# 2_port.net
KiCad netlist of a schematic drawn in EAGLE
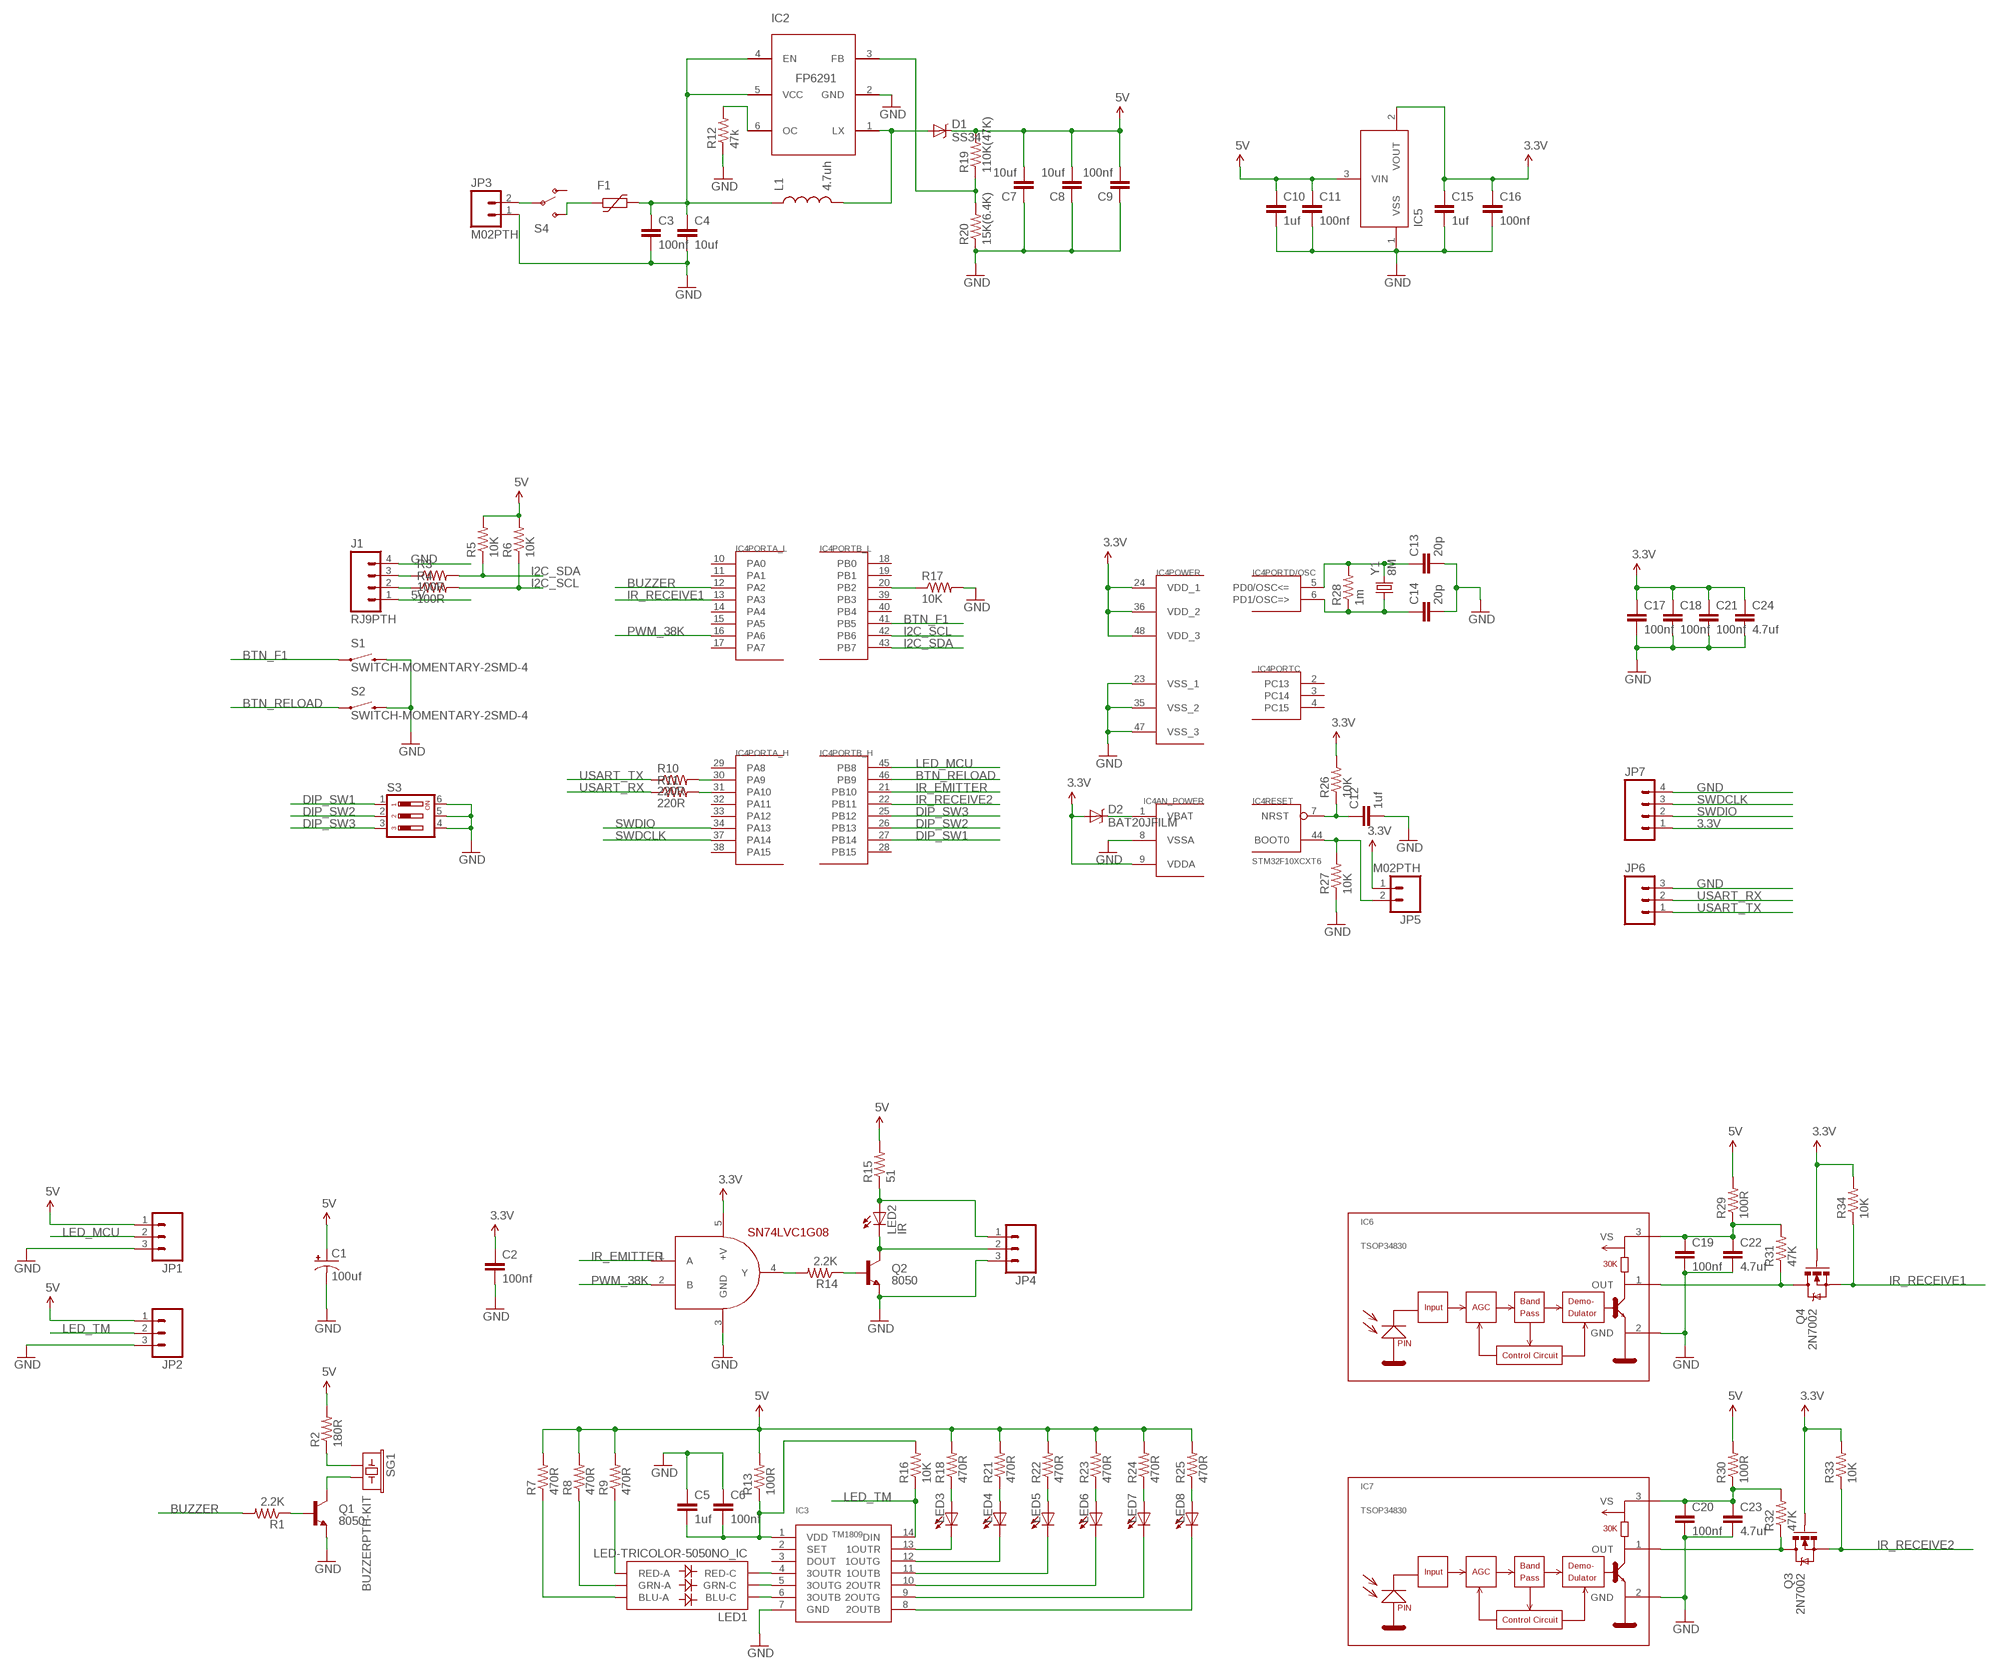
[diagram p0: schematic, sheet 1]

(export (version "E")
  (design (tool "Eeschema 10.0.6"))
  (components
    (comp (ref "C1")
      (value "100uf")
      (footprint "eagle-import:EIA6032")
      (libsource (lib "eagle-import") (part "CAP_POL6032"))
    )
    (comp (ref "C2")
      (value "100nf")
      (footprint "eagle-import:0603-CAP")
      (libsource (lib "eagle-import") (part "CAP0603-CAP"))
    )
    (comp (ref "C3")
      (value "100nf")
      (footprint "eagle-import:0603-CAP")
      (libsource (lib "eagle-import") (part "CAP0603-CAP"))
    )
    (comp (ref "C4")
      (value "10uf")
      (footprint "eagle-import:0603-CAP")
      (libsource (lib "eagle-import") (part "CAP0603-CAP"))
    )
    (comp (ref "C5")
      (value "1uf")
      (footprint "eagle-import:0603-CAP")
      (libsource (lib "eagle-import") (part "CAP0603-CAP"))
    )
    (comp (ref "C6")
      (value "100nf")
      (footprint "eagle-import:0603-CAP")
      (libsource (lib "eagle-import") (part "CAP0603-CAP"))
    )
    (comp (ref "C7")
      (value "10uf")
      (footprint "eagle-import:0603-CAP")
      (libsource (lib "eagle-import") (part "CAP0603-CAP"))
    )
    (comp (ref "C8")
      (value "10uf")
      (footprint "eagle-import:0603-CAP")
      (libsource (lib "eagle-import") (part "CAP0603-CAP"))
    )
    (comp (ref "C9")
      (value "100nf")
      (footprint "eagle-import:0603-CAP")
      (libsource (lib "eagle-import") (part "CAP0603-CAP"))
    )
    (comp (ref "C10")
      (value "1uf")
      (footprint "eagle-import:0603-CAP")
      (libsource (lib "eagle-import") (part "CAP0603-CAP"))
    )
    (comp (ref "C11")
      (value "100nf")
      (footprint "eagle-import:0603-CAP")
      (libsource (lib "eagle-import") (part "CAP0603-CAP"))
    )
    (comp (ref "C12")
      (value "1uf")
      (footprint "eagle-import:0603-CAP")
      (libsource (lib "eagle-import") (part "CAP0603-CAP"))
    )
    (comp (ref "C13")
      (value "20p")
      (footprint "eagle-import:0603-CAP")
      (libsource (lib "eagle-import") (part "CAP0603-CAP"))
    )
    (comp (ref "C14")
      (value "20p")
      (footprint "eagle-import:0603-CAP")
      (libsource (lib "eagle-import") (part "CAP0603-CAP"))
    )
    (comp (ref "C15")
      (value "1uf")
      (footprint "eagle-import:0603-CAP")
      (libsource (lib "eagle-import") (part "CAP0603-CAP"))
    )
    (comp (ref "C16")
      (value "100nf")
      (footprint "eagle-import:0603-CAP")
      (libsource (lib "eagle-import") (part "CAP0603-CAP"))
    )
    (comp (ref "C17")
      (value "100nf")
      (footprint "eagle-import:0603-CAP")
      (libsource (lib "eagle-import") (part "CAP0603-CAP"))
    )
    (comp (ref "C18")
      (value "100nf")
      (footprint "eagle-import:0603-CAP")
      (libsource (lib "eagle-import") (part "CAP0603-CAP"))
    )
    (comp (ref "C19")
      (value "100nf")
      (footprint "eagle-import:0603-CAP")
      (libsource (lib "eagle-import") (part "CAP0603-CAP"))
    )
    (comp (ref "C20")
      (value "100nf")
      (footprint "eagle-import:0603-CAP")
      (libsource (lib "eagle-import") (part "CAP0603-CAP"))
    )
    (comp (ref "C21")
      (value "100nf")
      (footprint "eagle-import:0603-CAP")
      (libsource (lib "eagle-import") (part "CAP0603-CAP"))
    )
    (comp (ref "C22")
      (value "4.7uf")
      (footprint "eagle-import:0603-CAP")
      (libsource (lib "eagle-import") (part "CAP0603-CAP"))
    )
    (comp (ref "C23")
      (value "4.7uf")
      (footprint "eagle-import:0603-CAP")
      (libsource (lib "eagle-import") (part "CAP0603-CAP"))
    )
    (comp (ref "C24")
      (value "4.7uf")
      (footprint "eagle-import:0603-CAP")
      (libsource (lib "eagle-import") (part "CAP0603-CAP"))
    )
    (comp (ref "D1")
      (value "SS34")
      (footprint "eagle-import:SMA-DIODE")
      (libsource (lib "eagle-import") (part "DIODE-SCHOTTKY_"))
    )
    (comp (ref "D2")
      (value "BAT20JFILM")
      (footprint "eagle-import:SOD-323")
      (libsource (lib "eagle-import") (part "BAT20JFILM"))
    )
    (comp (ref "F1")
      (value "PTC-FUSE")
      (footprint "eagle-import:R0805")
      (libsource (lib "eagle-import") (part "PTC-FUSE"))
    )
    (comp (ref "IC1")
      (value "SN74LVC1G08")
      (footprint "eagle-import:SOT23-5")
      (libsource (lib "eagle-import") (part "SN74LVC1G08"))
    )
    (comp (ref "IC2")
      (value "FP6291")
      (footprint "eagle-import:SOT23-6")
      (libsource (lib "eagle-import") (part "FP6291"))
    )
    (comp (ref "IC3")
      (value "TM1809")
      (footprint "eagle-import:SOP-14")
      (libsource (lib "eagle-import") (part "TM1809"))
    )
    (comp (ref "IC4")
      (value "STM32F10XCXT6")
      (footprint "eagle-import:TQFP48")
      (libsource (lib "eagle-import") (part "STM32F10XCXT6"))
    )
    (comp (ref "IC5")
      (value "XC6206")
      (footprint "eagle-import:SOT23-3")
      (libsource (lib "eagle-import") (part "XC6206"))
    )
    (comp (ref "IC6")
      (value "TSOP34830")
      (footprint "eagle-import:TSOP348")
      (libsource (lib "eagle-import") (part "TSOP34830"))
    )
    (comp (ref "IC7")
      (value "TSOP34830")
      (footprint "eagle-import:TSOP348")
      (libsource (lib "eagle-import") (part "TSOP34830"))
    )
    (comp (ref "J1")
      (value "RJ9PTH")
      (footprint "eagle-import:RJ9")
      (libsource (lib "eagle-import") (part "RJ9PTH"))
    )
    (comp (ref "JP1")
      (value "M03PTH")
      (footprint "eagle-import:1X03")
      (libsource (lib "eagle-import") (part "M03PTH"))
    )
    (comp (ref "JP2")
      (value "M03PTH")
      (footprint "eagle-import:1X03")
      (libsource (lib "eagle-import") (part "M03PTH"))
    )
    (comp (ref "JP3")
      (value "M02PTH")
      (footprint "eagle-import:1X02")
      (libsource (lib "eagle-import") (part "M02PTH"))
    )
    (comp (ref "JP4")
      (value "M03PTH")
      (footprint "eagle-import:1X03")
      (libsource (lib "eagle-import") (part "M03PTH"))
    )
    (comp (ref "JP5")
      (value "M02PTH")
      (footprint "eagle-import:1X02")
      (libsource (lib "eagle-import") (part "M02PTH"))
    )
    (comp (ref "JP6")
      (value "M03PTH")
      (footprint "eagle-import:1X03")
      (libsource (lib "eagle-import") (part "M03PTH"))
    )
    (comp (ref "JP7")
      (value "M04PTH")
      (footprint "eagle-import:1X04")
      (libsource (lib "eagle-import") (part "M04PTH"))
    )
    (comp (ref "L1")
      (value "4.7uh")
      (footprint "eagle-import:CR75_V2")
      (libsource (lib "eagle-import") (part "INDUCTORCR75_V2"))
    )
    (comp (ref "LED1")
      (value "LED-TRICOLOR-5050NO_IC")
      (footprint "eagle-import:LED-TRICOLOR-5050")
      (libsource (lib "eagle-import") (part "LED-TRICOLOR-5050NO_IC"))
    )
    (comp (ref "LED2")
      (value "IR")
      (footprint "eagle-import:LED5MM")
      (libsource (lib "eagle-import") (part "LED5MM"))
    )
    (comp (ref "LED3")
      (value "LED0805")
      (footprint "eagle-import:CHIPLED_0805")
      (libsource (lib "eagle-import") (part "LED0805"))
    )
    (comp (ref "LED4")
      (value "LED0805")
      (footprint "eagle-import:CHIPLED_0805")
      (libsource (lib "eagle-import") (part "LED0805"))
    )
    (comp (ref "LED5")
      (value "LED0805")
      (footprint "eagle-import:CHIPLED_0805")
      (libsource (lib "eagle-import") (part "LED0805"))
    )
    (comp (ref "LED6")
      (value "LED0805")
      (footprint "eagle-import:CHIPLED_0805")
      (libsource (lib "eagle-import") (part "LED0805"))
    )
    (comp (ref "LED7")
      (value "LED0805")
      (footprint "eagle-import:CHIPLED_0805")
      (libsource (lib "eagle-import") (part "LED0805"))
    )
    (comp (ref "LED8")
      (value "LED0805")
      (footprint "eagle-import:CHIPLED_0805")
      (libsource (lib "eagle-import") (part "LED0805"))
    )
    (comp (ref "Q1")
      (value "8050")
      (footprint "eagle-import:SOT23")
      (libsource (lib "eagle-import") (part "TRANSISTOR_NPNSOT23"))
    )
    (comp (ref "Q2")
      (value "8050")
      (footprint "eagle-import:SOT23")
      (libsource (lib "eagle-import") (part "TRANSISTOR_NPNSOT23"))
    )
    (comp (ref "Q3")
      (value "2N7002")
      (footprint "eagle-import:SOT23")
      (libsource (lib "eagle-import") (part "MOSFET-NCHANNELBSS138"))
    )
    (comp (ref "Q4")
      (value "2N7002")
      (footprint "eagle-import:SOT23")
      (libsource (lib "eagle-import") (part "MOSFET-NCHANNELBSS138"))
    )
    (comp (ref "R1")
      (value "2.2K")
      (footprint "eagle-import:0603-RES")
      (libsource (lib "eagle-import") (part "RESISTOR0603-RES"))
    )
    (comp (ref "R2")
      (value "180R")
      (footprint "eagle-import:0603-RES")
      (libsource (lib "eagle-import") (part "RESISTOR0603-RES"))
    )
    (comp (ref "R3")
      (value "100R")
      (footprint "eagle-import:0603-RES")
      (libsource (lib "eagle-import") (part "RESISTOR0603-RES"))
    )
    (comp (ref "R4")
      (value "100R")
      (footprint "eagle-import:0603-RES")
      (libsource (lib "eagle-import") (part "RESISTOR0603-RES"))
    )
    (comp (ref "R5")
      (value "10K")
      (footprint "eagle-import:0603-RES")
      (libsource (lib "eagle-import") (part "RESISTOR0603-RES"))
    )
    (comp (ref "R6")
      (value "10K")
      (footprint "eagle-import:0603-RES")
      (libsource (lib "eagle-import") (part "RESISTOR0603-RES"))
    )
    (comp (ref "R7")
      (value "470R")
      (footprint "eagle-import:0603-RES")
      (libsource (lib "eagle-import") (part "RESISTOR0603-RES"))
    )
    (comp (ref "R8")
      (value "470R")
      (footprint "eagle-import:0603-RES")
      (libsource (lib "eagle-import") (part "RESISTOR0603-RES"))
    )
    (comp (ref "R9")
      (value "470R")
      (footprint "eagle-import:0603-RES")
      (libsource (lib "eagle-import") (part "RESISTOR0603-RES"))
    )
    (comp (ref "R10")
      (value "220R")
      (footprint "eagle-import:0603-RES")
      (libsource (lib "eagle-import") (part "RESISTOR0603-RES"))
    )
    (comp (ref "R11")
      (value "220R")
      (footprint "eagle-import:0603-RES")
      (libsource (lib "eagle-import") (part "RESISTOR0603-RES"))
    )
    (comp (ref "R12")
      (value "47k")
      (footprint "eagle-import:0603-RES")
      (libsource (lib "eagle-import") (part "RESISTOR0603-RES"))
    )
    (comp (ref "R13")
      (value "100R")
      (footprint "eagle-import:0603-RES")
      (libsource (lib "eagle-import") (part "RESISTOR0603-RES"))
    )
    (comp (ref "R14")
      (value "2.2K")
      (footprint "eagle-import:0603-RES")
      (libsource (lib "eagle-import") (part "RESISTOR0603-RES"))
    )
    (comp (ref "R15")
      (value "51")
      (footprint "eagle-import:1206")
      (libsource (lib "eagle-import") (part "SparkFun-Resistors_RESISTOR1206"))
    )
    (comp (ref "R16")
      (value "10K")
      (footprint "eagle-import:0603-RES")
      (libsource (lib "eagle-import") (part "RESISTOR0603-RES"))
    )
    (comp (ref "R17")
      (value "10K")
      (footprint "eagle-import:0603-RES")
      (libsource (lib "eagle-import") (part "RESISTOR0603-RES"))
    )
    (comp (ref "R18")
      (value "470R")
      (footprint "eagle-import:0603-RES")
      (libsource (lib "eagle-import") (part "RESISTOR0603-RES"))
    )
    (comp (ref "R19")
      (value "110K(47K)")
      (footprint "eagle-import:0603-RES")
      (libsource (lib "eagle-import") (part "RESISTOR0603-RES"))
    )
    (comp (ref "R20")
      (value "15K(6.4K)")
      (footprint "eagle-import:0603-RES")
      (libsource (lib "eagle-import") (part "RESISTOR0603-RES"))
    )
    (comp (ref "R21")
      (value "470R")
      (footprint "eagle-import:0603-RES")
      (libsource (lib "eagle-import") (part "RESISTOR0603-RES"))
    )
    (comp (ref "R22")
      (value "470R")
      (footprint "eagle-import:0603-RES")
      (libsource (lib "eagle-import") (part "RESISTOR0603-RES"))
    )
    (comp (ref "R23")
      (value "470R")
      (footprint "eagle-import:0603-RES")
      (libsource (lib "eagle-import") (part "RESISTOR0603-RES"))
    )
    (comp (ref "R24")
      (value "470R")
      (footprint "eagle-import:0603-RES")
      (libsource (lib "eagle-import") (part "RESISTOR0603-RES"))
    )
    (comp (ref "R25")
      (value "470R")
      (footprint "eagle-import:0603-RES")
      (libsource (lib "eagle-import") (part "RESISTOR0603-RES"))
    )
    (comp (ref "R26")
      (value "10K")
      (footprint "eagle-import:0603-RES")
      (libsource (lib "eagle-import") (part "RESISTOR0603-RES"))
    )
    (comp (ref "R27")
      (value "10K")
      (footprint "eagle-import:0603-RES")
      (libsource (lib "eagle-import") (part "RESISTOR0603-RES"))
    )
    (comp (ref "R28")
      (value "1m")
      (footprint "eagle-import:0603-RES")
      (libsource (lib "eagle-import") (part "RESISTOR0603-RES"))
    )
    (comp (ref "R29")
      (value "100R")
      (footprint "eagle-import:0603-RES")
      (libsource (lib "eagle-import") (part "RESISTOR0603-RES"))
    )
    (comp (ref "R30")
      (value "100R")
      (footprint "eagle-import:0603-RES")
      (libsource (lib "eagle-import") (part "RESISTOR0603-RES"))
    )
    (comp (ref "R31")
      (value "47K")
      (footprint "eagle-import:0603-RES")
      (libsource (lib "eagle-import") (part "RESISTOR0603-RES"))
    )
    (comp (ref "R32")
      (value "47K")
      (footprint "eagle-import:0603-RES")
      (libsource (lib "eagle-import") (part "RESISTOR0603-RES"))
    )
    (comp (ref "R33")
      (value "10K")
      (footprint "eagle-import:0603-RES")
      (libsource (lib "eagle-import") (part "RESISTOR0603-RES"))
    )
    (comp (ref "R34")
      (value "10K")
      (footprint "eagle-import:0603-RES")
      (libsource (lib "eagle-import") (part "RESISTOR0603-RES"))
    )
    (comp (ref "S1")
      (value "SWITCH-MOMENTARY-2SMD-4")
      (footprint "eagle-import:TACTILE_SWITCH_TALL")
      (libsource (lib "eagle-import") (part "SWITCH-MOMENTARY-2SMD-4"))
    )
    (comp (ref "S2")
      (value "SWITCH-MOMENTARY-2SMD-4")
      (footprint "eagle-import:TACTILE_SWITCH_TALL")
      (libsource (lib "eagle-import") (part "SWITCH-MOMENTARY-2SMD-4"))
    )
    (comp (ref "S3")
      (value "DIP03YL")
      (footprint "eagle-import:DIP03YL")
      (libsource (lib "eagle-import") (part "DIP03YL"))
    )
    (comp (ref "S4")
      (value "SWITCH-SPST3AM6")
      (footprint "eagle-import:SWITCH-SPDT-AM#6")
      (libsource (lib "eagle-import") (part "SWITCH-SPST3AM6"))
    )
    (comp (ref "SG1")
      (value "BUZZERPTH-KIT")
      (footprint "eagle-import:BUZZER-12MM-KIT")
      (libsource (lib "eagle-import") (part "BUZZERPTH-KIT"))
    )
    (comp (ref "Y1")
      (value "8M")
      (footprint "eagle-import:CRYSTAL-TXC-7A")
      (libsource (lib "eagle-import") (part "CRYSTALTXC-7A"))
    )
  )
  (nets
    (net (code "1") (name "/BTN_F1") (class "Default")
      (node (ref "IC4") (pin "41") (pinfunction "PB5_41") (pintype "bidirectional"))
      (node (ref "S1") (pin "A2") (pinfunction "1_A2") (pintype "passive"))
    )
    (net (code "2") (name "/BTN_RELOAD") (class "Default")
      (node (ref "IC4") (pin "46") (pinfunction "PB9_46") (pintype "bidirectional"))
      (node (ref "S2") (pin "A2") (pinfunction "1_A2") (pintype "passive"))
    )
    (net (code "3") (name "/BUZZER") (class "Default")
      (node (ref "IC4") (pin "12") (pinfunction "PA2_12") (pintype "bidirectional"))
      (node (ref "R1") (pin "2") (pinfunction "2_2") (pintype "passive"))
    )
    (net (code "4") (name "/DIP_SW1") (class "Default")
      (node (ref "IC4") (pin "27") (pinfunction "PB14_27") (pintype "bidirectional"))
      (node (ref "S3") (pin "1") (pinfunction "1_1") (pintype "passive"))
    )
    (net (code "5") (name "/DIP_SW2") (class "Default")
      (node (ref "IC4") (pin "26") (pinfunction "PB13_26") (pintype "bidirectional"))
      (node (ref "S3") (pin "2") (pinfunction "2_2") (pintype "passive"))
    )
    (net (code "6") (name "/DIP_SW3") (class "Default")
      (node (ref "IC4") (pin "25") (pinfunction "PB12_25") (pintype "bidirectional"))
      (node (ref "S3") (pin "3") (pinfunction "3_3") (pintype "passive"))
    )
    (net (code "7") (name "/I2C_SCL") (class "Default")
      (node (ref "IC4") (pin "42") (pinfunction "PB6_42") (pintype "bidirectional"))
      (node (ref "R4") (pin "2") (pinfunction "2_2") (pintype "passive"))
      (node (ref "R6") (pin "1") (pinfunction "1_1") (pintype "passive"))
    )
    (net (code "8") (name "/I2C_SDA") (class "Default")
      (node (ref "IC4") (pin "43") (pinfunction "PB7_43") (pintype "bidirectional"))
      (node (ref "R3") (pin "2") (pinfunction "2_2") (pintype "passive"))
      (node (ref "R5") (pin "1") (pinfunction "1_1") (pintype "passive"))
    )
    (net (code "9") (name "/IR_EMITTER") (class "Default")
      (node (ref "IC1") (pin "1") (pinfunction "A_1") (pintype "bidirectional"))
      (node (ref "IC4") (pin "21") (pinfunction "PB10_21") (pintype "bidirectional"))
    )
    (net (code "10") (name "/IR_RECEIVE1") (class "Default")
      (node (ref "IC4") (pin "13") (pinfunction "PA3_13") (pintype "bidirectional"))
      (node (ref "Q4") (pin "2") (pinfunction "S_2") (pintype "passive"))
      (node (ref "R34") (pin "1") (pinfunction "1_1") (pintype "passive"))
    )
    (net (code "11") (name "/IR_RECEIVE2") (class "Default")
      (node (ref "IC4") (pin "22") (pinfunction "PB11_22") (pintype "bidirectional"))
      (node (ref "Q3") (pin "2") (pinfunction "S_2") (pintype "passive"))
      (node (ref "R33") (pin "1") (pinfunction "1_1") (pintype "passive"))
    )
    (net (code "12") (name "/LED_MCU") (class "Default")
      (node (ref "IC4") (pin "45") (pinfunction "PB8_45") (pintype "bidirectional"))
      (node (ref "JP1") (pin "2") (pinfunction "2_2") (pintype "passive"))
    )
    (net (code "13") (name "/LED_TM") (class "Default")
      (node (ref "IC3") (pin "14") (pinfunction "DIN_14") (pintype "input"))
      (node (ref "JP2") (pin "2") (pinfunction "2_2") (pintype "passive"))
      (node (ref "R16") (pin "1") (pinfunction "1_1") (pintype "passive"))
    )
    (net (code "14") (name "/PWM_38K") (class "Default")
      (node (ref "IC1") (pin "2") (pinfunction "B_2") (pintype "bidirectional"))
      (node (ref "IC4") (pin "16") (pinfunction "PA6_16") (pintype "bidirectional"))
    )
    (net (code "15") (name "/SWDCLK") (class "Default")
      (node (ref "IC4") (pin "37") (pinfunction "PA14_37") (pintype "bidirectional"))
      (node (ref "JP7") (pin "3") (pinfunction "3_3") (pintype "passive"))
    )
    (net (code "16") (name "/SWDIO") (class "Default")
      (node (ref "IC4") (pin "34") (pinfunction "PA13_34") (pintype "bidirectional"))
      (node (ref "JP7") (pin "2") (pinfunction "2_2") (pintype "passive"))
    )
    (net (code "17") (name "/USART_RX") (class "Default")
      (node (ref "JP6") (pin "2") (pinfunction "2_2") (pintype "passive"))
      (node (ref "R11") (pin "1") (pinfunction "1_1") (pintype "passive"))
    )
    (net (code "18") (name "/USART_TX") (class "Default")
      (node (ref "JP6") (pin "1") (pinfunction "1_1") (pintype "passive"))
      (node (ref "R10") (pin "1") (pinfunction "1_1") (pintype "passive"))
    )
    (net (code "19") (name "3.3V") (class "Default")
      (node (ref "C15") (pin "1") (pinfunction "1_1") (pintype "passive"))
      (node (ref "C16") (pin "1") (pinfunction "1_1") (pintype "passive"))
      (node (ref "C17") (pin "1") (pinfunction "1_1") (pintype "passive"))
      (node (ref "C18") (pin "1") (pinfunction "1_1") (pintype "passive"))
      (node (ref "C2") (pin "1") (pinfunction "1_1") (pintype "passive"))
      (node (ref "C21") (pin "1") (pinfunction "1_1") (pintype "passive"))
      (node (ref "C24") (pin "1") (pinfunction "1_1") (pintype "passive"))
      (node (ref "D2") (pin "2") (pinfunction "A_2") (pintype "passive"))
      (node (ref "IC1") (pin "5") (pinfunction "+V_5") (pintype "bidirectional"))
      (node (ref "IC4") (pin "24") (pinfunction "VDD_1_24") (pintype "power_in"))
      (node (ref "IC4") (pin "36") (pinfunction "VDD_2_36") (pintype "power_in"))
      (node (ref "IC4") (pin "48") (pinfunction "VDD_3_48") (pintype "power_in"))
      (node (ref "IC4") (pin "9") (pinfunction "VDDA_9") (pintype "power_in"))
      (node (ref "IC5") (pin "2") (pinfunction "VOUT_2") (pintype "power_in"))
      (node (ref "JP5") (pin "1") (pinfunction "1_1") (pintype "passive"))
      (node (ref "JP7") (pin "1") (pinfunction "1_1") (pintype "passive"))
      (node (ref "Q3") (pin "1") (pinfunction "G_1") (pintype "passive"))
      (node (ref "Q4") (pin "1") (pinfunction "G_1") (pintype "passive"))
      (node (ref "R26") (pin "2") (pinfunction "2_2") (pintype "passive"))
      (node (ref "R33") (pin "2") (pinfunction "2_2") (pintype "passive"))
      (node (ref "R34") (pin "2") (pinfunction "2_2") (pintype "passive"))
    )
    (net (code "20") (name "5V") (class "Default")
      (node (ref "C1") (pin "P$1") (pinfunction "+_P$1") (pintype "passive"))
      (node (ref "C10") (pin "1") (pinfunction "1_1") (pintype "passive"))
      (node (ref "C11") (pin "1") (pinfunction "1_1") (pintype "passive"))
      (node (ref "C7") (pin "2") (pinfunction "2_2") (pintype "passive"))
      (node (ref "C8") (pin "2") (pinfunction "2_2") (pintype "passive"))
      (node (ref "C9") (pin "2") (pinfunction "2_2") (pintype "passive"))
      (node (ref "D1") (pin "C") (pinfunction "C_C") (pintype "passive"))
      (node (ref "IC5") (pin "3") (pinfunction "VIN_3") (pintype "power_in"))
      (node (ref "J1") (pin "1") (pinfunction "1_1") (pintype "passive"))
      (node (ref "JP1") (pin "1") (pinfunction "1_1") (pintype "passive"))
      (node (ref "JP2") (pin "1") (pinfunction "1_1") (pintype "passive"))
      (node (ref "R13") (pin "2") (pinfunction "2_2") (pintype "passive"))
      (node (ref "R15") (pin "2") (pinfunction "2_2") (pintype "passive"))
      (node (ref "R18") (pin "2") (pinfunction "2_2") (pintype "passive"))
      (node (ref "R19") (pin "2") (pinfunction "2_2") (pintype "passive"))
      (node (ref "R2") (pin "2") (pinfunction "2_2") (pintype "passive"))
      (node (ref "R21") (pin "2") (pinfunction "2_2") (pintype "passive"))
      (node (ref "R22") (pin "2") (pinfunction "2_2") (pintype "passive"))
      (node (ref "R23") (pin "2") (pinfunction "2_2") (pintype "passive"))
      (node (ref "R24") (pin "2") (pinfunction "2_2") (pintype "passive"))
      (node (ref "R25") (pin "2") (pinfunction "2_2") (pintype "passive"))
      (node (ref "R29") (pin "2") (pinfunction "2_2") (pintype "passive"))
      (node (ref "R30") (pin "2") (pinfunction "2_2") (pintype "passive"))
      (node (ref "R5") (pin "2") (pinfunction "2_2") (pintype "passive"))
      (node (ref "R6") (pin "2") (pinfunction "2_2") (pintype "passive"))
      (node (ref "R7") (pin "2") (pinfunction "2_2") (pintype "passive"))
      (node (ref "R8") (pin "2") (pinfunction "2_2") (pintype "passive"))
      (node (ref "R9") (pin "2") (pinfunction "2_2") (pintype "passive"))
    )
    (net (code "21") (name "GND") (class "Default")
      (node (ref "C1") (pin "P$2") (pinfunction "-_P$2") (pintype "passive"))
      (node (ref "C10") (pin "2") (pinfunction "2_2") (pintype "passive"))
      (node (ref "C11") (pin "2") (pinfunction "2_2") (pintype "passive"))
      (node (ref "C12") (pin "2") (pinfunction "2_2") (pintype "passive"))
      (node (ref "C13") (pin "2") (pinfunction "2_2") (pintype "passive"))
      (node (ref "C14") (pin "2") (pinfunction "2_2") (pintype "passive"))
      (node (ref "C15") (pin "2") (pinfunction "2_2") (pintype "passive"))
      (node (ref "C16") (pin "2") (pinfunction "2_2") (pintype "passive"))
      (node (ref "C17") (pin "2") (pinfunction "2_2") (pintype "passive"))
      (node (ref "C18") (pin "2") (pinfunction "2_2") (pintype "passive"))
      (node (ref "C19") (pin "2") (pinfunction "2_2") (pintype "passive"))
      (node (ref "C2") (pin "2") (pinfunction "2_2") (pintype "passive"))
      (node (ref "C20") (pin "2") (pinfunction "2_2") (pintype "passive"))
      (node (ref "C21") (pin "2") (pinfunction "2_2") (pintype "passive"))
      (node (ref "C22") (pin "2") (pinfunction "2_2") (pintype "passive"))
      (node (ref "C23") (pin "2") (pinfunction "2_2") (pintype "passive"))
      (node (ref "C24") (pin "2") (pinfunction "2_2") (pintype "passive"))
      (node (ref "C3") (pin "2") (pinfunction "2_2") (pintype "passive"))
      (node (ref "C4") (pin "2") (pinfunction "2_2") (pintype "passive"))
      (node (ref "C5") (pin "1") (pinfunction "1_1") (pintype "passive"))
      (node (ref "C6") (pin "1") (pinfunction "1_1") (pintype "passive"))
      (node (ref "C7") (pin "1") (pinfunction "1_1") (pintype "passive"))
      (node (ref "C8") (pin "1") (pinfunction "1_1") (pintype "passive"))
      (node (ref "C9") (pin "1") (pinfunction "1_1") (pintype "passive"))
      (node (ref "IC1") (pin "3") (pinfunction "GND_3") (pintype "bidirectional"))
      (node (ref "IC2") (pin "2") (pinfunction "GND_2") (pintype "power_in"))
      (node (ref "IC3") (pin "7") (pinfunction "GND_7") (pintype "power_in"))
      (node (ref "IC4") (pin "23") (pinfunction "VSS_1_23") (pintype "power_in"))
      (node (ref "IC4") (pin "35") (pinfunction "VSS_2_35") (pintype "power_in"))
      (node (ref "IC4") (pin "47") (pinfunction "VSS_3_47") (pintype "power_in"))
      (node (ref "IC4") (pin "8") (pinfunction "VSSA_8") (pintype "power_in"))
      (node (ref "IC5") (pin "1") (pinfunction "VSS_1") (pintype "power_in"))
      (node (ref "IC6") (pin "2") (pinfunction "GND_2") (pintype "power_in"))
      (node (ref "IC7") (pin "2") (pinfunction "GND_2") (pintype "power_in"))
      (node (ref "J1") (pin "4") (pinfunction "4_4") (pintype "passive"))
      (node (ref "JP1") (pin "3") (pinfunction "3_3") (pintype "passive"))
      (node (ref "JP2") (pin "3") (pinfunction "3_3") (pintype "passive"))
      (node (ref "JP3") (pin "1") (pinfunction "1_1") (pintype "passive"))
      (node (ref "JP4") (pin "3") (pinfunction "3_3") (pintype "passive"))
      (node (ref "JP6") (pin "3") (pinfunction "3_3") (pintype "passive"))
      (node (ref "JP7") (pin "4") (pinfunction "4_4") (pintype "passive"))
      (node (ref "Q1") (pin "2") (pinfunction "E_2") (pintype "passive"))
      (node (ref "Q2") (pin "2") (pinfunction "E_2") (pintype "passive"))
      (node (ref "R12") (pin "1") (pinfunction "1_1") (pintype "passive"))
      (node (ref "R17") (pin "2") (pinfunction "2_2") (pintype "passive"))
      (node (ref "R20") (pin "1") (pinfunction "1_1") (pintype "passive"))
      (node (ref "R27") (pin "1") (pinfunction "1_1") (pintype "passive"))
      (node (ref "S1") (pin "B2") (pinfunction "2_B2") (pintype "passive"))
      (node (ref "S2") (pin "B2") (pinfunction "2_B2") (pintype "passive"))
      (node (ref "S3") (pin "4") (pinfunction "4_4") (pintype "passive"))
      (node (ref "S3") (pin "5") (pinfunction "5_5") (pintype "passive"))
      (node (ref "S3") (pin "6") (pinfunction "6_6") (pintype "passive"))
    )
    (net (code "22") (name "Net-(D2-C)") (class "Default")
      (node (ref "D2") (pin "1") (pinfunction "C_1") (pintype "passive"))
      (node (ref "IC4") (pin "1") (pinfunction "VBAT_1") (pintype "power_in"))
    )
    (net (code "23") (name "Net-(IC1-Y)") (class "Default")
      (node (ref "IC1") (pin "4") (pinfunction "Y_4") (pintype "bidirectional"))
      (node (ref "R14") (pin "2") (pinfunction "2_2") (pintype "passive"))
    )
    (net (code "24") (name "Net-(IC2-EN)") (class "Default")
      (node (ref "C3") (pin "1") (pinfunction "1_1") (pintype "passive"))
      (node (ref "C4") (pin "1") (pinfunction "1_1") (pintype "passive"))
      (node (ref "F1") (pin "2") (pinfunction "2_2") (pintype "passive"))
      (node (ref "IC2") (pin "4") (pinfunction "EN_4") (pintype "bidirectional"))
      (node (ref "IC2") (pin "5") (pinfunction "VCC_5") (pintype "power_in"))
      (node (ref "L1") (pin "P$1") (pinfunction "1_P$1") (pintype "passive"))
    )
    (net (code "25") (name "Net-(IC2-FB)") (class "Default")
      (node (ref "IC2") (pin "3") (pinfunction "FB_3") (pintype "bidirectional"))
      (node (ref "R19") (pin "1") (pinfunction "1_1") (pintype "passive"))
      (node (ref "R20") (pin "2") (pinfunction "2_2") (pintype "passive"))
    )
    (net (code "26") (name "Net-(IC2-LX)") (class "Default")
      (node (ref "D1") (pin "A") (pinfunction "A_A") (pintype "passive"))
      (node (ref "IC2") (pin "1") (pinfunction "LX_1") (pintype "bidirectional"))
      (node (ref "L1") (pin "P$2") (pinfunction "2_P$2") (pintype "passive"))
    )
    (net (code "27") (name "Net-(IC2-OC)") (class "Default")
      (node (ref "IC2") (pin "6") (pinfunction "OC_6") (pintype "open_collector"))
      (node (ref "R12") (pin "2") (pinfunction "2_2") (pintype "passive"))
    )
    (net (code "28") (name "Net-(IC3-1OUTB)") (class "Default")
      (node (ref "IC3") (pin "11") (pinfunction "1OUTB_11") (pintype "output"))
      (node (ref "LED5") (pin "C") (pinfunction "C_C") (pintype "passive"))
    )
    (net (code "29") (name "Net-(IC3-1OUTG)") (class "Default")
      (node (ref "IC3") (pin "12") (pinfunction "1OUTG_12") (pintype "output"))
      (node (ref "LED4") (pin "C") (pinfunction "C_C") (pintype "passive"))
    )
    (net (code "30") (name "Net-(IC3-1OUTR)") (class "Default")
      (node (ref "IC3") (pin "13") (pinfunction "1OUTR_13") (pintype "output"))
      (node (ref "LED3") (pin "C") (pinfunction "C_C") (pintype "passive"))
    )
    (net (code "31") (name "Net-(IC3-2OUTB)") (class "Default")
      (node (ref "IC3") (pin "8") (pinfunction "2OUTB_8") (pintype "output"))
      (node (ref "LED8") (pin "C") (pinfunction "C_C") (pintype "passive"))
    )
    (net (code "32") (name "Net-(IC3-2OUTG)") (class "Default")
      (node (ref "IC3") (pin "9") (pinfunction "2OUTG_9") (pintype "output"))
      (node (ref "LED7") (pin "C") (pinfunction "C_C") (pintype "passive"))
    )
    (net (code "33") (name "Net-(IC3-2OUTR)") (class "Default")
      (node (ref "IC3") (pin "10") (pinfunction "2OUTR_10") (pintype "output"))
      (node (ref "LED6") (pin "C") (pinfunction "C_C") (pintype "passive"))
    )
    (net (code "34") (name "Net-(IC3-3OUTB)") (class "Default")
      (node (ref "IC3") (pin "6") (pinfunction "3OUTB_6") (pintype "output"))
      (node (ref "LED1") (pin "4") (pinfunction "BLU-C_4") (pintype "bidirectional"))
    )
    (net (code "35") (name "Net-(IC3-3OUTG)") (class "Default")
      (node (ref "IC3") (pin "5") (pinfunction "3OUTG_5") (pintype "output"))
      (node (ref "LED1") (pin "6") (pinfunction "GRN-C_6") (pintype "bidirectional"))
    )
    (net (code "36") (name "Net-(IC3-3OUTR)") (class "Default")
      (node (ref "IC3") (pin "4") (pinfunction "3OUTR_4") (pintype "output"))
      (node (ref "LED1") (pin "5") (pinfunction "RED-C_5") (pintype "bidirectional"))
    )
    (net (code "37") (name "Net-(IC3-VDD)") (class "Default")
      (node (ref "C5") (pin "2") (pinfunction "2_2") (pintype "passive"))
      (node (ref "C6") (pin "2") (pinfunction "2_2") (pintype "passive"))
      (node (ref "IC3") (pin "1") (pinfunction "VDD_1") (pintype "power_in"))
      (node (ref "R13") (pin "1") (pinfunction "1_1") (pintype "passive"))
      (node (ref "R16") (pin "2") (pinfunction "2_2") (pintype "passive"))
    )
    (net (code "38") (name "Net-(IC4B-PA9)") (class "Default")
      (node (ref "IC4") (pin "30") (pinfunction "PA9_30") (pintype "bidirectional"))
      (node (ref "R10") (pin "2") (pinfunction "2_2") (pintype "passive"))
    )
    (net (code "39") (name "Net-(IC4B-PA10)") (class "Default")
      (node (ref "IC4") (pin "31") (pinfunction "PA10_31") (pintype "bidirectional"))
      (node (ref "R11") (pin "2") (pinfunction "2_2") (pintype "passive"))
    )
    (net (code "40") (name "Net-(IC4E-PB2)") (class "Default")
      (node (ref "IC4") (pin "20") (pinfunction "PB2_20") (pintype "bidirectional"))
      (node (ref "R17") (pin "1") (pinfunction "1_1") (pintype "passive"))
    )
    (net (code "41") (name "Net-(IC4G-PD0{slash}OSC<=)") (class "Default")
      (node (ref "C13") (pin "1") (pinfunction "1_1") (pintype "passive"))
      (node (ref "IC4") (pin "5") (pinfunction "PD0/OSC<=_5") (pintype "bidirectional"))
      (node (ref "R28") (pin "2") (pinfunction "2_2") (pintype "passive"))
      (node (ref "Y1") (pin "P$2") (pinfunction "2_P$2") (pintype "passive"))
    )
    (net (code "42") (name "Net-(IC4G-PD1{slash}OSC=>)") (class "Default")
      (node (ref "C14") (pin "1") (pinfunction "1_1") (pintype "passive"))
      (node (ref "IC4") (pin "6") (pinfunction "PD1/OSC=>_6") (pintype "bidirectional"))
      (node (ref "R28") (pin "1") (pinfunction "1_1") (pintype "passive"))
      (node (ref "Y1") (pin "P$1") (pinfunction "1_P$1") (pintype "passive"))
    )
    (net (code "43") (name "Net-(IC4I-BOOT0)") (class "Default")
      (node (ref "IC4") (pin "44") (pinfunction "BOOT0_44") (pintype "input"))
      (node (ref "JP5") (pin "2") (pinfunction "2_2") (pintype "passive"))
      (node (ref "R27") (pin "2") (pinfunction "2_2") (pintype "passive"))
    )
    (net (code "44") (name "Net-(IC4I-NRST)") (class "Default")
      (node (ref "C12") (pin "1") (pinfunction "1_1") (pintype "passive"))
      (node (ref "IC4") (pin "7") (pinfunction "NRST_7") (pintype "input"))
      (node (ref "R26") (pin "1") (pinfunction "1_1") (pintype "passive"))
    )
    (net (code "45") (name "Net-(IC6-OUT)") (class "Default")
      (node (ref "IC6") (pin "1") (pinfunction "OUT_1") (pintype "output"))
      (node (ref "Q4") (pin "3") (pinfunction "D_3") (pintype "passive"))
      (node (ref "R31") (pin "1") (pinfunction "1_1") (pintype "passive"))
    )
    (net (code "46") (name "Net-(IC6-VS)") (class "Default")
      (node (ref "C19") (pin "1") (pinfunction "1_1") (pintype "passive"))
      (node (ref "C22") (pin "1") (pinfunction "1_1") (pintype "passive"))
      (node (ref "IC6") (pin "3") (pinfunction "VS_3") (pintype "power_in"))
      (node (ref "R29") (pin "1") (pinfunction "1_1") (pintype "passive"))
      (node (ref "R31") (pin "2") (pinfunction "2_2") (pintype "passive"))
    )
    (net (code "47") (name "Net-(IC7-OUT)") (class "Default")
      (node (ref "IC7") (pin "1") (pinfunction "OUT_1") (pintype "output"))
      (node (ref "Q3") (pin "3") (pinfunction "D_3") (pintype "passive"))
      (node (ref "R32") (pin "1") (pinfunction "1_1") (pintype "passive"))
    )
    (net (code "48") (name "Net-(IC7-VS)") (class "Default")
      (node (ref "C20") (pin "1") (pinfunction "1_1") (pintype "passive"))
      (node (ref "C23") (pin "1") (pinfunction "1_1") (pintype "passive"))
      (node (ref "IC7") (pin "3") (pinfunction "VS_3") (pintype "power_in"))
      (node (ref "R30") (pin "1") (pinfunction "1_1") (pintype "passive"))
      (node (ref "R32") (pin "2") (pinfunction "2_2") (pintype "passive"))
    )
    (net (code "49") (name "Net-(J1-Pad2)") (class "Default")
      (node (ref "J1") (pin "2") (pinfunction "2_2") (pintype "passive"))
      (node (ref "R4") (pin "1") (pinfunction "1_1") (pintype "passive"))
    )
    (net (code "50") (name "Net-(J1-Pad3)") (class "Default")
      (node (ref "J1") (pin "3") (pinfunction "3_3") (pintype "passive"))
      (node (ref "R3") (pin "1") (pinfunction "1_1") (pintype "passive"))
    )
    (net (code "51") (name "Net-(JP4-Pad1)") (class "Default")
      (node (ref "JP4") (pin "1") (pinfunction "1_1") (pintype "passive"))
      (node (ref "LED2") (pin "A") (pinfunction "A_A") (pintype "passive"))
      (node (ref "R15") (pin "1") (pinfunction "1_1") (pintype "passive"))
    )
    (net (code "52") (name "Net-(LED1-BLU-A)") (class "Default")
      (node (ref "LED1") (pin "3") (pinfunction "BLU-A_3") (pintype "bidirectional"))
      (node (ref "R7") (pin "1") (pinfunction "1_1") (pintype "passive"))
    )
    (net (code "53") (name "Net-(LED1-GRN-A)") (class "Default")
      (node (ref "LED1") (pin "1") (pinfunction "GRN-A_1") (pintype "bidirectional"))
      (node (ref "R8") (pin "1") (pinfunction "1_1") (pintype "passive"))
    )
    (net (code "54") (name "Net-(LED1-RED-A)") (class "Default")
      (node (ref "LED1") (pin "2") (pinfunction "RED-A_2") (pintype "bidirectional"))
      (node (ref "R9") (pin "1") (pinfunction "1_1") (pintype "passive"))
    )
    (net (code "55") (name "Net-(LED2-C)") (class "Default")
      (node (ref "JP4") (pin "2") (pinfunction "2_2") (pintype "passive"))
      (node (ref "LED2") (pin "K") (pinfunction "C_K") (pintype "passive"))
      (node (ref "Q2") (pin "3") (pinfunction "C_3") (pintype "passive"))
    )
    (net (code "56") (name "Net-(LED3-PadA)") (class "Default")
      (node (ref "LED3") (pin "A") (pinfunction "A_A") (pintype "passive"))
      (node (ref "R18") (pin "1") (pinfunction "1_1") (pintype "passive"))
    )
    (net (code "57") (name "Net-(LED4-PadA)") (class "Default")
      (node (ref "LED4") (pin "A") (pinfunction "A_A") (pintype "passive"))
      (node (ref "R21") (pin "1") (pinfunction "1_1") (pintype "passive"))
    )
    (net (code "58") (name "Net-(LED5-PadA)") (class "Default")
      (node (ref "LED5") (pin "A") (pinfunction "A_A") (pintype "passive"))
      (node (ref "R22") (pin "1") (pinfunction "1_1") (pintype "passive"))
    )
    (net (code "59") (name "Net-(LED6-PadA)") (class "Default")
      (node (ref "LED6") (pin "A") (pinfunction "A_A") (pintype "passive"))
      (node (ref "R23") (pin "1") (pinfunction "1_1") (pintype "passive"))
    )
    (net (code "60") (name "Net-(LED7-PadA)") (class "Default")
      (node (ref "LED7") (pin "A") (pinfunction "A_A") (pintype "passive"))
      (node (ref "R24") (pin "1") (pinfunction "1_1") (pintype "passive"))
    )
    (net (code "61") (name "Net-(LED8-PadA)") (class "Default")
      (node (ref "LED8") (pin "A") (pinfunction "A_A") (pintype "passive"))
      (node (ref "R25") (pin "1") (pinfunction "1_1") (pintype "passive"))
    )
    (net (code "62") (name "Net-(Q1-B)") (class "Default")
      (node (ref "Q1") (pin "1") (pinfunction "B_1") (pintype "passive"))
      (node (ref "R1") (pin "1") (pinfunction "1_1") (pintype "passive"))
    )
    (net (code "63") (name "Net-(Q1-C)") (class "Default")
      (node (ref "Q1") (pin "3") (pinfunction "C_3") (pintype "passive"))
      (node (ref "SG1") (pin "-") (pinfunction "2_-") (pintype "passive"))
    )
    (net (code "64") (name "Net-(Q2-B)") (class "Default")
      (node (ref "Q2") (pin "1") (pinfunction "B_1") (pintype "passive"))
      (node (ref "R14") (pin "1") (pinfunction "1_1") (pintype "passive"))
    )
    (net (code "65") (name "Net-(S4-P)") (class "Default")
      (node (ref "JP3") (pin "2") (pinfunction "2_2") (pintype "passive"))
      (node (ref "S4") (pin "2") (pinfunction "P_2") (pintype "passive"))
    )
    (net (code "66") (name "Net-(S4-S)") (class "Default")
      (node (ref "F1") (pin "1") (pinfunction "1_1") (pintype "passive"))
      (node (ref "S4") (pin "3") (pinfunction "S_3") (pintype "passive"))
    )
    (net (code "67") (name "Net-(SG1-1)") (class "Default")
      (node (ref "R2") (pin "1") (pinfunction "1_1") (pintype "passive"))
      (node (ref "SG1") (pin "+") (pinfunction "1_+") (pintype "passive"))
    )
    (net (code "68") (name "unconnected-(IC3-DOUT-Pad3)") (class "Default")
      (node (ref "IC3") (pin "3") (pinfunction "DOUT_3") (pintype "output"))
    )
    (net (code "69") (name "unconnected-(IC3-SET-Pad2)") (class "Default")
      (node (ref "IC3") (pin "2") (pinfunction "SET_2") (pintype "input"))
    )
    (net (code "70") (name "unconnected-(IC4B-PA8-Pad29)") (class "Default")
      (node (ref "IC4") (pin "29") (pinfunction "PA8_29") (pintype "bidirectional"))
    )
    (net (code "71") (name "unconnected-(IC4B-PA11-Pad32)") (class "Default")
      (node (ref "IC4") (pin "32") (pinfunction "PA11_32") (pintype "bidirectional"))
    )
    (net (code "72") (name "unconnected-(IC4B-PA12-Pad33)") (class "Default")
      (node (ref "IC4") (pin "33") (pinfunction "PA12_33") (pintype "bidirectional"))
    )
    (net (code "73") (name "unconnected-(IC4B-PA15-Pad38)") (class "Default")
      (node (ref "IC4") (pin "38") (pinfunction "PA15_38") (pintype "bidirectional"))
    )
    (net (code "74") (name "unconnected-(IC4C-PA0-Pad10)") (class "Default")
      (node (ref "IC4") (pin "10") (pinfunction "PA0_10") (pintype "bidirectional"))
    )
    (net (code "75") (name "unconnected-(IC4C-PA1-Pad11)") (class "Default")
      (node (ref "IC4") (pin "11") (pinfunction "PA1_11") (pintype "bidirectional"))
    )
    (net (code "76") (name "unconnected-(IC4C-PA4-Pad14)") (class "Default")
      (node (ref "IC4") (pin "14") (pinfunction "PA4_14") (pintype "bidirectional"))
    )
    (net (code "77") (name "unconnected-(IC4C-PA5-Pad15)") (class "Default")
      (node (ref "IC4") (pin "15") (pinfunction "PA5_15") (pintype "bidirectional"))
    )
    (net (code "78") (name "unconnected-(IC4C-PA7-Pad17)") (class "Default")
      (node (ref "IC4") (pin "17") (pinfunction "PA7_17") (pintype "bidirectional"))
    )
    (net (code "79") (name "unconnected-(IC4D-PB15-Pad28)") (class "Default")
      (node (ref "IC4") (pin "28") (pinfunction "PB15_28") (pintype "bidirectional"))
    )
    (net (code "80") (name "unconnected-(IC4E-PB0-Pad18)") (class "Default")
      (node (ref "IC4") (pin "18") (pinfunction "PB0_18") (pintype "bidirectional"))
    )
    (net (code "81") (name "unconnected-(IC4E-PB1-Pad19)") (class "Default")
      (node (ref "IC4") (pin "19") (pinfunction "PB1_19") (pintype "bidirectional"))
    )
    (net (code "82") (name "unconnected-(IC4E-PB3-Pad39)") (class "Default")
      (node (ref "IC4") (pin "39") (pinfunction "PB3_39") (pintype "bidirectional"))
    )
    (net (code "83") (name "unconnected-(IC4E-PB4-Pad40)") (class "Default")
      (node (ref "IC4") (pin "40") (pinfunction "PB4_40") (pintype "bidirectional"))
    )
    (net (code "84") (name "unconnected-(IC4F-PC13-Pad2)") (class "Default")
      (node (ref "IC4") (pin "2") (pinfunction "PC13_2") (pintype "bidirectional"))
    )
    (net (code "85") (name "unconnected-(IC4F-PC14-Pad3)") (class "Default")
      (node (ref "IC4") (pin "3") (pinfunction "PC14_3") (pintype "bidirectional"))
    )
    (net (code "86") (name "unconnected-(IC4F-PC15-Pad4)") (class "Default")
      (node (ref "IC4") (pin "4") (pinfunction "PC15_4") (pintype "bidirectional"))
    )
    (net (code "87") (name "unconnected-(S4-O-Pad1)") (class "Default")
      (node (ref "S4") (pin "1") (pinfunction "O_1") (pintype "passive"))
    )
  )
)
